# Adafruit_Feather_nRF52840_Rev.net
KiCad netlist of a schematic drawn in EAGLE
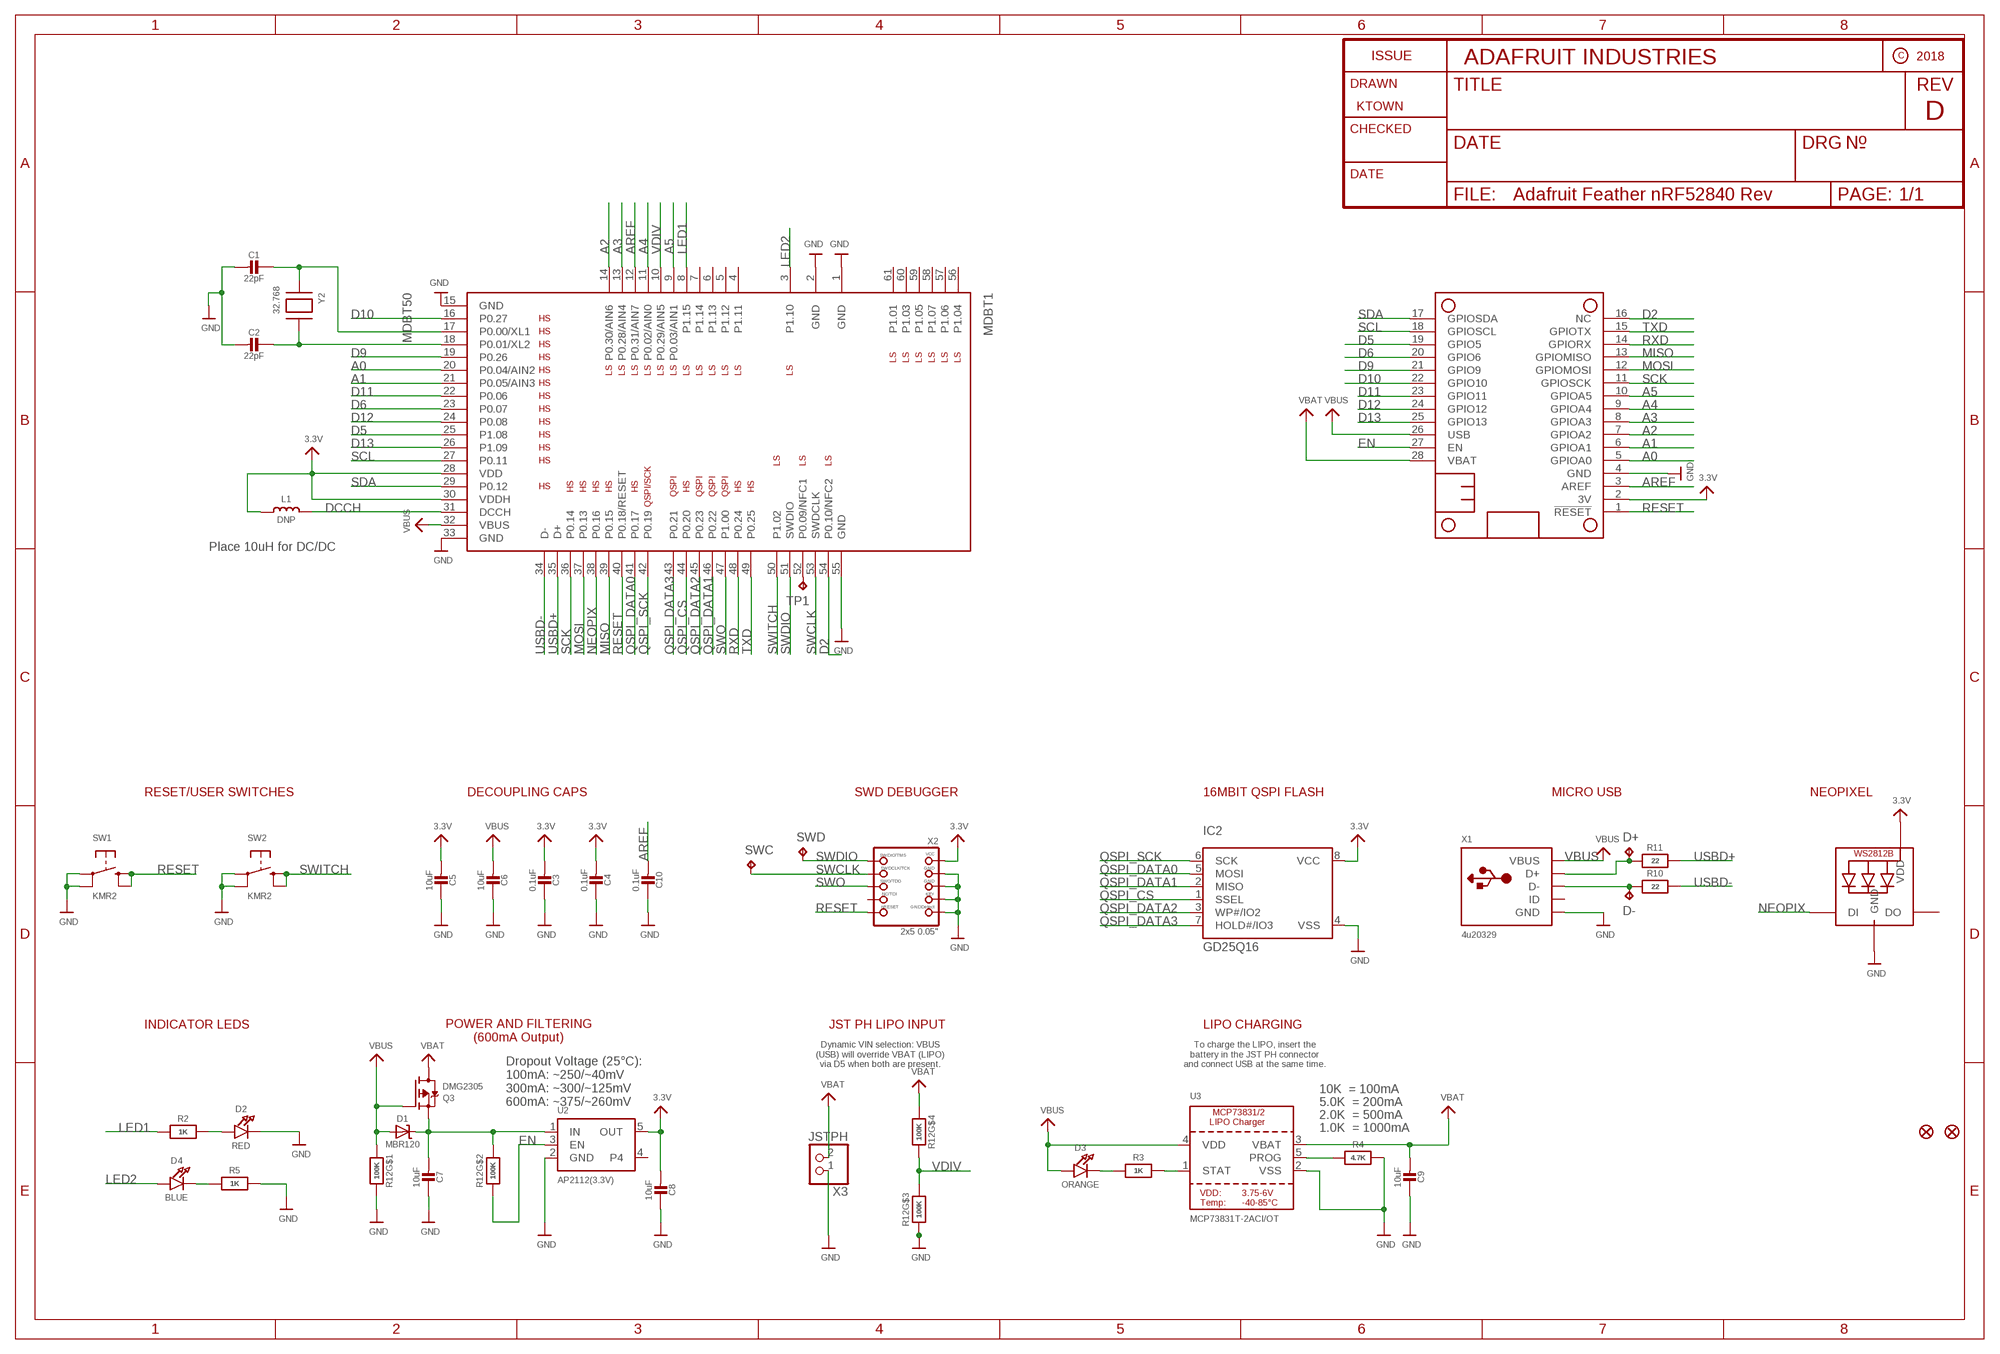
[diagram p0: schematic, sheet 1]

(export (version "E")
  (design (tool "Eeschema 10.0.6"))
  (components
    (comp (ref "C1")
      (value "22pF")
      (footprint "eagle-import:0603-NO")
      (libsource (lib "eagle-import") (part "CAP_CERAMIC0603_NO"))
    )
    (comp (ref "C2")
      (value "22pF")
      (footprint "eagle-import:0603-NO")
      (libsource (lib "eagle-import") (part "CAP_CERAMIC0603_NO"))
    )
    (comp (ref "C3")
      (value "0.1uF")
      (footprint "eagle-import:0603-NO")
      (libsource (lib "eagle-import") (part "CAP_CERAMIC0603_NO"))
    )
    (comp (ref "C4")
      (value "0.1uF")
      (footprint "eagle-import:0603-NO")
      (libsource (lib "eagle-import") (part "CAP_CERAMIC0603_NO"))
    )
    (comp (ref "C5")
      (value "10uF")
      (footprint "eagle-import:0805-NO")
      (libsource (lib "eagle-import") (part "CAP_CERAMIC0805-NOOUTLINE"))
    )
    (comp (ref "C6")
      (value "10uF")
      (footprint "eagle-import:0805-NO")
      (libsource (lib "eagle-import") (part "CAP_CERAMIC0805-NOOUTLINE"))
    )
    (comp (ref "C7")
      (value "10uF")
      (footprint "eagle-import:0805-NO")
      (libsource (lib "eagle-import") (part "CAP_CERAMIC0805-NOOUTLINE"))
    )
    (comp (ref "C8")
      (value "10uF")
      (footprint "eagle-import:0805-NO")
      (libsource (lib "eagle-import") (part "CAP_CERAMIC0805-NOOUTLINE"))
    )
    (comp (ref "C9")
      (value "10uF")
      (footprint "eagle-import:0805-NO")
      (libsource (lib "eagle-import") (part "CAP_CERAMIC0805-NOOUTLINE"))
    )
    (comp (ref "C10")
      (value "0.1uF")
      (footprint "eagle-import:0603-NO")
      (libsource (lib "eagle-import") (part "CAP_CERAMIC0603_NO"))
    )
    (comp (ref "D+")
      (value "TPTP10R")
      (footprint "eagle-import:TP10R")
      (libsource (lib "eagle-import") (part "TPTP10R"))
    )
    (comp (ref "D-")
      (value "TPTP10R")
      (footprint "eagle-import:TP10R")
      (libsource (lib "eagle-import") (part "TPTP10R"))
    )
    (comp (ref "D1")
      (value "MBR120")
      (footprint "eagle-import:SOD-123")
      (libsource (lib "eagle-import") (part "DIODE-SCHOTTKYSOD-123"))
    )
    (comp (ref "D2")
      (value "RED")
      (footprint "eagle-import:CHIPLED_0805_NOOUTLINE")
      (libsource (lib "eagle-import") (part "LED0805_NOOUTLINE"))
    )
    (comp (ref "D3")
      (value "ORANGE")
      (footprint "eagle-import:CHIPLED_0805_NOOUTLINE")
      (libsource (lib "eagle-import") (part "LED0805_NOOUTLINE"))
    )
    (comp (ref "D4")
      (value "BLUE")
      (footprint "eagle-import:CHIPLED_0805_NOOUTLINE")
      (libsource (lib "eagle-import") (part "LED0805_NOOUTLINE"))
    )
    (comp (ref "FID1")
      (value "FIDUCIAL_1MM")
      (footprint "eagle-import:FIDUCIAL_1MM")
      (libsource (lib "eagle-import") (part "FIDUCIAL_1MM"))
    )
    (comp (ref "FID2")
      (value "FIDUCIAL_1MM")
      (footprint "eagle-import:FIDUCIAL_1MM")
      (libsource (lib "eagle-import") (part "FIDUCIAL_1MM"))
    )
    (comp (ref "IC2")
      (value "GD25Q16")
      (footprint "eagle-import:USON8")
      (libsource (lib "eagle-import") (part "SPIFLASH_8PINUX"))
    )
    (comp (ref "L1")
      (value "DNP")
      (footprint "eagle-import:_0805MP")
      (libsource (lib "eagle-import") (part "INDUCTOR_0805MP"))
    )
    (comp (ref "LED1")
      (value "WS2812B3535")
      (footprint "eagle-import:LED3535")
      (libsource (lib "eagle-import") (part "WS2812B3535"))
    )
    (comp (ref "MDBT1")
      (value "MDBT50")
      (footprint "eagle-import:MDBT50")
      (libsource (lib "eagle-import") (part "MDBT50"))
    )
    (comp (ref "MS1")
      (value "FEATHERWING_NODIM")
      (footprint "eagle-import:FEATHERWING_NODIM")
      (libsource (lib "eagle-import") (part "FEATHERWING_NODIM"))
    )
    (comp (ref "Q3")
      (value "DMG2305")
      (footprint "eagle-import:SOT23-R")
      (libsource (lib "eagle-import") (part "MOSFET-P"))
    )
    (comp (ref "R2")
      (value "1K")
      (footprint "eagle-import:0603-NO")
      (libsource (lib "eagle-import") (part "RESISTOR_0603_NOOUT"))
    )
    (comp (ref "R3")
      (value "1K")
      (footprint "eagle-import:0603-NO")
      (libsource (lib "eagle-import") (part "RESISTOR_0603_NOOUT"))
    )
    (comp (ref "R4")
      (value "4.7K")
      (footprint "eagle-import:0603-NO")
      (libsource (lib "eagle-import") (part "RESISTOR_0603_NOOUT"))
    )
    (comp (ref "R5")
      (value "1K")
      (footprint "eagle-import:0603-NO")
      (libsource (lib "eagle-import") (part "RESISTOR_0603_NOOUT"))
    )
    (comp (ref "R10")
      (value "22")
      (footprint "eagle-import:0603-NO")
      (libsource (lib "eagle-import") (part "RESISTOR_0603_NOOUT"))
    )
    (comp (ref "R11")
      (value "22")
      (footprint "eagle-import:0603-NO")
      (libsource (lib "eagle-import") (part "RESISTOR_0603_NOOUT"))
    )
    (comp (ref "R12")
      (value "100K")
      (footprint "eagle-import:RESPACK_4X0603")
      (libsource (lib "eagle-import") (part "RESISTOR_4PACK"))
    )
    (comp (ref "SW1")
      (value "KMR2")
      (footprint "eagle-import:BTN_KMR2_4.6X2.8")
      (libsource (lib "eagle-import") (part "SWITCH_TACT_SMT4.6X2.8"))
    )
    (comp (ref "SW2")
      (value "KMR2")
      (footprint "eagle-import:BTN_KMR2_4.6X2.8")
      (libsource (lib "eagle-import") (part "SWITCH_TACT_SMT4.6X2.8"))
    )
    (comp (ref "SWC")
      (value "TPTP12R")
      (footprint "eagle-import:TP12R")
      (libsource (lib "eagle-import") (part "TPTP12R"))
    )
    (comp (ref "SWD")
      (value "TPTP12R")
      (footprint "eagle-import:TP12R")
      (libsource (lib "eagle-import") (part "TPTP12R"))
    )
    (comp (ref "TP1")
      (value "TPTP10R")
      (footprint "eagle-import:TP10R")
      (libsource (lib "eagle-import") (part "TPTP10R"))
    )
    (comp (ref "U2")
      (value "AP2112(3.3V)")
      (footprint "eagle-import:SOT23-5")
      (libsource (lib "eagle-import") (part "VREG_SOT23-5"))
    )
    (comp (ref "U3")
      (value "MCP73831T-2ACI/OT")
      (footprint "eagle-import:SOT23-5")
      (libsource (lib "eagle-import") (part "MCP73831/2"))
    )
    (comp (ref "X1")
      (value "4u20329")
      (footprint "eagle-import:4UCONN_20329_V2")
      (libsource (lib "eagle-import") (part "USB_MICRO_20329_V2"))
    )
    (comp (ref "X2")
      (value "2x5 0.05\"")
      (footprint "eagle-import:2X05_1.27MM_BOX_POSTS")
      (libsource (lib "eagle-import") (part "JTAG-CORTEXBOXPOSTS"))
    )
    (comp (ref "X3")
      (value "JSTPH")
      (footprint "eagle-import:JSTPH2")
      (libsource (lib "eagle-import") (part "CON_JST_PH_2PIN"))
    )
    (comp (ref "Y2")
      (value "32.768")
      (footprint "eagle-import:XTAL3215")
      (libsource (lib "eagle-import") (part "XTAL-3.2X1.5"))
    )
  )
  (nets
    (net (code "1") (name "/A0") (class "Default")
      (node (ref "MDBT1") (pin "20") (pinfunction "P0.04/AIN2_20") (pintype "bidirectional"))
      (node (ref "MS1") (pin "5") (pinfunction "GPIOA0_5") (pintype "bidirectional"))
    )
    (net (code "2") (name "/A1") (class "Default")
      (node (ref "MDBT1") (pin "21") (pinfunction "P0.05/AIN3_21") (pintype "bidirectional"))
      (node (ref "MS1") (pin "6") (pinfunction "GPIOA1_6") (pintype "bidirectional"))
    )
    (net (code "3") (name "/A2") (class "Default")
      (node (ref "MDBT1") (pin "14") (pinfunction "P0.30/AIN6_14") (pintype "bidirectional"))
      (node (ref "MS1") (pin "7") (pinfunction "GPIOA2_7") (pintype "bidirectional"))
    )
    (net (code "4") (name "/A3") (class "Default")
      (node (ref "MDBT1") (pin "13") (pinfunction "P0.28/AIN4_13") (pintype "bidirectional"))
      (node (ref "MS1") (pin "8") (pinfunction "GPIOA3_8") (pintype "bidirectional"))
    )
    (net (code "5") (name "/A4") (class "Default")
      (node (ref "MDBT1") (pin "11") (pinfunction "P0.02/AIN0_11") (pintype "bidirectional"))
      (node (ref "MS1") (pin "9") (pinfunction "GPIOA4_9") (pintype "bidirectional"))
    )
    (net (code "6") (name "/A5") (class "Default")
      (node (ref "MDBT1") (pin "9") (pinfunction "P0.03/AIN1_9") (pintype "bidirectional"))
      (node (ref "MS1") (pin "10") (pinfunction "GPIOA5_10") (pintype "bidirectional"))
    )
    (net (code "7") (name "/AREF") (class "Default")
      (node (ref "C10") (pin "2") (pinfunction "2_2") (pintype "passive"))
      (node (ref "MDBT1") (pin "12") (pinfunction "P0.31/AIN7_12") (pintype "bidirectional"))
      (node (ref "MS1") (pin "3") (pinfunction "AREF_3") (pintype "passive"))
    )
    (net (code "8") (name "/D2") (class "Default")
      (node (ref "MDBT1") (pin "54") (pinfunction "P0.10/NFC2_54") (pintype "bidirectional"))
      (node (ref "MS1") (pin "16") (pinfunction "NC_16") (pintype "passive"))
    )
    (net (code "9") (name "/D5") (class "Default")
      (node (ref "MDBT1") (pin "25") (pinfunction "P1.08_25") (pintype "bidirectional"))
      (node (ref "MS1") (pin "19") (pinfunction "GPIO5_19") (pintype "bidirectional"))
    )
    (net (code "10") (name "/D6") (class "Default")
      (node (ref "MDBT1") (pin "23") (pinfunction "P0.07_23") (pintype "bidirectional"))
      (node (ref "MS1") (pin "20") (pinfunction "GPIO6_20") (pintype "bidirectional"))
    )
    (net (code "11") (name "/D9") (class "Default")
      (node (ref "MDBT1") (pin "19") (pinfunction "P0.26_19") (pintype "bidirectional"))
      (node (ref "MS1") (pin "21") (pinfunction "GPIO9_21") (pintype "bidirectional"))
    )
    (net (code "12") (name "/D10") (class "Default")
      (node (ref "MDBT1") (pin "16") (pinfunction "P0.27_16") (pintype "bidirectional"))
      (node (ref "MS1") (pin "22") (pinfunction "GPIO10_22") (pintype "bidirectional"))
    )
    (net (code "13") (name "/D11") (class "Default")
      (node (ref "MDBT1") (pin "22") (pinfunction "P0.06_22") (pintype "bidirectional"))
      (node (ref "MS1") (pin "23") (pinfunction "GPIO11_23") (pintype "bidirectional"))
    )
    (net (code "14") (name "/D12") (class "Default")
      (node (ref "MDBT1") (pin "24") (pinfunction "P0.08_24") (pintype "bidirectional"))
      (node (ref "MS1") (pin "24") (pinfunction "GPIO12_24") (pintype "bidirectional"))
    )
    (net (code "15") (name "/D13") (class "Default")
      (node (ref "MDBT1") (pin "26") (pinfunction "P1.09_26") (pintype "bidirectional"))
      (node (ref "MS1") (pin "25") (pinfunction "GPIO13_25") (pintype "bidirectional"))
    )
    (net (code "16") (name "/DCCH") (class "Default")
      (node (ref "L1") (pin "2") (pinfunction "2_2") (pintype "passive"))
      (node (ref "MDBT1") (pin "31") (pinfunction "DCCH_31") (pintype "bidirectional"))
    )
    (net (code "17") (name "/EN") (class "Default")
      (node (ref "MS1") (pin "27") (pinfunction "EN_27") (pintype "passive"))
      (node (ref "R12") (pin "2") (pinfunction "1_2") (pintype "passive"))
      (node (ref "U2") (pin "3") (pinfunction "EN_3") (pintype "input"))
    )
    (net (code "18") (name "/LED1") (class "Default")
      (node (ref "MDBT1") (pin "8") (pinfunction "P1.15_8") (pintype "bidirectional"))
      (node (ref "R2") (pin "1") (pinfunction "1_1") (pintype "passive"))
    )
    (net (code "19") (name "/LED2") (class "Default")
      (node (ref "D4") (pin "A") (pinfunction "A_A") (pintype "passive"))
      (node (ref "MDBT1") (pin "3") (pinfunction "P1.10_3") (pintype "bidirectional"))
    )
    (net (code "20") (name "/MISO") (class "Default")
      (node (ref "MDBT1") (pin "39") (pinfunction "P0.15_39") (pintype "bidirectional"))
      (node (ref "MS1") (pin "13") (pinfunction "GPIOMISO_13") (pintype "bidirectional"))
    )
    (net (code "21") (name "/MOSI") (class "Default")
      (node (ref "MDBT1") (pin "37") (pinfunction "P0.13_37") (pintype "bidirectional"))
      (node (ref "MS1") (pin "12") (pinfunction "GPIOMOSI_12") (pintype "bidirectional"))
    )
    (net (code "22") (name "/NEOPIX") (class "Default")
      (node (ref "LED1") (pin "1") (pinfunction "DI_1") (pintype "input"))
      (node (ref "MDBT1") (pin "38") (pinfunction "P0.16_38") (pintype "bidirectional"))
    )
    (net (code "23") (name "/QSPI_CS") (class "Default")
      (node (ref "IC2") (pin "1") (pinfunction "SSEL_1") (pintype "bidirectional"))
      (node (ref "MDBT1") (pin "44") (pinfunction "P0.20_44") (pintype "bidirectional"))
    )
    (net (code "24") (name "/QSPI_DATA0") (class "Default")
      (node (ref "IC2") (pin "5") (pinfunction "MOSI_5") (pintype "bidirectional"))
      (node (ref "MDBT1") (pin "41") (pinfunction "P0.17_41") (pintype "bidirectional"))
    )
    (net (code "25") (name "/QSPI_DATA1") (class "Default")
      (node (ref "IC2") (pin "2") (pinfunction "MISO_2") (pintype "bidirectional"))
      (node (ref "MDBT1") (pin "46") (pinfunction "P0.22_46") (pintype "bidirectional"))
    )
    (net (code "26") (name "/QSPI_DATA2") (class "Default")
      (node (ref "IC2") (pin "3") (pinfunction "WP#/IO2_3") (pintype "bidirectional"))
      (node (ref "MDBT1") (pin "45") (pinfunction "P0.23_45") (pintype "bidirectional"))
    )
    (net (code "27") (name "/QSPI_DATA3") (class "Default")
      (node (ref "IC2") (pin "7") (pinfunction "HOLD#/IO3_7") (pintype "bidirectional"))
      (node (ref "MDBT1") (pin "43") (pinfunction "P0.21_43") (pintype "bidirectional"))
    )
    (net (code "28") (name "/QSPI_SCK") (class "Default")
      (node (ref "IC2") (pin "6") (pinfunction "SCK_6") (pintype "bidirectional"))
      (node (ref "MDBT1") (pin "42") (pinfunction "P0.19_42") (pintype "bidirectional"))
    )
    (net (code "29") (name "/RESET") (class "Default")
      (node (ref "MDBT1") (pin "40") (pinfunction "P0.18/RESET_40") (pintype "bidirectional"))
      (node (ref "MS1") (pin "1") (pinfunction "~{RESET}_1") (pintype "input"))
      (node (ref "SW1") (pin "B") (pinfunction "S_B") (pintype "passive"))
      (node (ref "SW1") (pin "B'") (pinfunction "S1_B'") (pintype "passive"))
      (node (ref "X2") (pin "10") (pinfunction "NRESET_10") (pintype "bidirectional"))
    )
    (net (code "30") (name "/RXD") (class "Default")
      (node (ref "MDBT1") (pin "48") (pinfunction "P0.24_48") (pintype "bidirectional"))
      (node (ref "MS1") (pin "14") (pinfunction "GPIORX_14") (pintype "bidirectional"))
    )
    (net (code "31") (name "/SCK") (class "Default")
      (node (ref "MDBT1") (pin "36") (pinfunction "P0.14_36") (pintype "bidirectional"))
      (node (ref "MS1") (pin "11") (pinfunction "GPIOSCK_11") (pintype "bidirectional"))
    )
    (net (code "32") (name "/SCL") (class "Default")
      (node (ref "MDBT1") (pin "27") (pinfunction "P0.11_27") (pintype "bidirectional"))
      (node (ref "MS1") (pin "18") (pinfunction "GPIOSCL_18") (pintype "bidirectional"))
    )
    (net (code "33") (name "/SDA") (class "Default")
      (node (ref "MDBT1") (pin "29") (pinfunction "P0.12_29") (pintype "bidirectional"))
      (node (ref "MS1") (pin "17") (pinfunction "GPIOSDA_17") (pintype "bidirectional"))
    )
    (net (code "34") (name "/SWCLK") (class "Default")
      (node (ref "MDBT1") (pin "53") (pinfunction "SWDCLK_53") (pintype "bidirectional"))
      (node (ref "SWC") (pin "TP") (pinfunction "TP_TP") (pintype "input"))
      (node (ref "X2") (pin "4") (pinfunction "SWDCLK_4") (pintype "bidirectional"))
    )
    (net (code "35") (name "/SWDIO") (class "Default")
      (node (ref "MDBT1") (pin "51") (pinfunction "SWDIO_51") (pintype "bidirectional"))
      (node (ref "SWD") (pin "TP") (pinfunction "TP_TP") (pintype "input"))
      (node (ref "X2") (pin "2") (pinfunction "SWDIO_2") (pintype "bidirectional"))
    )
    (net (code "36") (name "/SWITCH") (class "Default")
      (node (ref "MDBT1") (pin "50") (pinfunction "P1.02_50") (pintype "bidirectional"))
      (node (ref "SW2") (pin "B") (pinfunction "S_B") (pintype "passive"))
      (node (ref "SW2") (pin "B'") (pinfunction "S1_B'") (pintype "passive"))
    )
    (net (code "37") (name "/SWO") (class "Default")
      (node (ref "MDBT1") (pin "47") (pinfunction "P1.00_47") (pintype "bidirectional"))
      (node (ref "X2") (pin "6") (pinfunction "SWO_6") (pintype "bidirectional"))
    )
    (net (code "38") (name "/TXD") (class "Default")
      (node (ref "MDBT1") (pin "49") (pinfunction "P0.25_49") (pintype "bidirectional"))
      (node (ref "MS1") (pin "15") (pinfunction "GPIOTX_15") (pintype "bidirectional"))
    )
    (net (code "39") (name "/USBD+") (class "Default")
      (node (ref "MDBT1") (pin "35") (pinfunction "D+_35") (pintype "bidirectional"))
      (node (ref "R11") (pin "2") (pinfunction "2_2") (pintype "passive"))
    )
    (net (code "40") (name "/USBD-") (class "Default")
      (node (ref "MDBT1") (pin "34") (pinfunction "D-_34") (pintype "bidirectional"))
      (node (ref "R10") (pin "2") (pinfunction "2_2") (pintype "passive"))
    )
    (net (code "41") (name "/VDIV") (class "Default")
      (node (ref "MDBT1") (pin "10") (pinfunction "P0.29/AIN5_10") (pintype "bidirectional"))
      (node (ref "R12") (pin "5") (pinfunction "2_5") (pintype "passive"))
      (node (ref "R12") (pin "6") (pinfunction "2_6") (pintype "passive"))
    )
    (net (code "42") (name "3.3V") (class "Default")
      (node (ref "C3") (pin "2") (pinfunction "2_2") (pintype "passive"))
      (node (ref "C4") (pin "2") (pinfunction "2_2") (pintype "passive"))
      (node (ref "C5") (pin "2") (pinfunction "2_2") (pintype "passive"))
      (node (ref "C8") (pin "2") (pinfunction "2_2") (pintype "passive"))
      (node (ref "IC2") (pin "8") (pinfunction "VCC_8") (pintype "bidirectional"))
      (node (ref "L1") (pin "1") (pinfunction "1_1") (pintype "passive"))
      (node (ref "LED1") (pin "2") (pinfunction "VDD_2") (pintype "power_in"))
      (node (ref "MDBT1") (pin "28") (pinfunction "VDD_28") (pintype "bidirectional"))
      (node (ref "MDBT1") (pin "30") (pinfunction "VDDH_30") (pintype "bidirectional"))
      (node (ref "MS1") (pin "2") (pinfunction "3V_2") (pintype "power_in"))
      (node (ref "U2") (pin "5") (pinfunction "OUT_5") (pintype "power_in"))
      (node (ref "X2") (pin "1") (pinfunction "VCC_1") (pintype "power_in"))
    )
    (net (code "43") (name "GND") (class "Default")
      (node (ref "C1") (pin "2") (pinfunction "2_2") (pintype "passive"))
      (node (ref "C10") (pin "1") (pinfunction "1_1") (pintype "passive"))
      (node (ref "C2") (pin "2") (pinfunction "2_2") (pintype "passive"))
      (node (ref "C3") (pin "1") (pinfunction "1_1") (pintype "passive"))
      (node (ref "C4") (pin "1") (pinfunction "1_1") (pintype "passive"))
      (node (ref "C5") (pin "1") (pinfunction "1_1") (pintype "passive"))
      (node (ref "C6") (pin "1") (pinfunction "1_1") (pintype "passive"))
      (node (ref "C7") (pin "1") (pinfunction "1_1") (pintype "passive"))
      (node (ref "C8") (pin "1") (pinfunction "1_1") (pintype "passive"))
      (node (ref "C9") (pin "1") (pinfunction "1_1") (pintype "passive"))
      (node (ref "D2") (pin "C") (pinfunction "C_C") (pintype "passive"))
      (node (ref "IC2") (pin "4") (pinfunction "VSS_4") (pintype "bidirectional"))
      (node (ref "LED1") (pin "4") (pinfunction "GND_4") (pintype "power_in"))
      (node (ref "MDBT1") (pin "1") (pinfunction "GND_1") (pintype "bidirectional"))
      (node (ref "MDBT1") (pin "15") (pinfunction "GND_15") (pintype "bidirectional"))
      (node (ref "MDBT1") (pin "2") (pinfunction "GND_2") (pintype "bidirectional"))
      (node (ref "MDBT1") (pin "33") (pinfunction "GND_33") (pintype "bidirectional"))
      (node (ref "MDBT1") (pin "55") (pinfunction "GND_55") (pintype "bidirectional"))
      (node (ref "MS1") (pin "4") (pinfunction "GND_4") (pintype "power_in"))
      (node (ref "R12") (pin "3") (pinfunction "1_3") (pintype "passive"))
      (node (ref "R12") (pin "8") (pinfunction "2_8") (pintype "passive"))
      (node (ref "R4") (pin "2") (pinfunction "2_2") (pintype "passive"))
      (node (ref "R5") (pin "2") (pinfunction "2_2") (pintype "passive"))
      (node (ref "SW1") (pin "A") (pinfunction "P_A") (pintype "passive"))
      (node (ref "SW1") (pin "A'") (pinfunction "P1_A'") (pintype "passive"))
      (node (ref "SW2") (pin "A") (pinfunction "P_A") (pintype "passive"))
      (node (ref "SW2") (pin "A'") (pinfunction "P1_A'") (pintype "passive"))
      (node (ref "U2") (pin "2") (pinfunction "GND_2") (pintype "power_in"))
      (node (ref "U3") (pin "2") (pinfunction "VSS_2") (pintype "power_in"))
      (node (ref "X1") (pin "BASE@1") (pinfunction "GND_BASE@1") (pintype "power_in"))
      (node (ref "X1") (pin "BASE@2") (pinfunction "GND_BASE@2") (pintype "power_in"))
      (node (ref "X1") (pin "GND") (pinfunction "GND_GND") (pintype "power_in"))
      (node (ref "X1") (pin "SPRT@1") (pinfunction "GND_SPRT@1") (pintype "power_in"))
      (node (ref "X1") (pin "SPRT@2") (pinfunction "GND_SPRT@2") (pintype "power_in"))
      (node (ref "X1") (pin "SPRT@3") (pinfunction "GND_SPRT@3") (pintype "power_in"))
      (node (ref "X1") (pin "SPRT@4") (pinfunction "GND_SPRT@4") (pintype "power_in"))
      (node (ref "X2") (pin "3") (pinfunction "GND_3") (pintype "power_in"))
      (node (ref "X2") (pin "5") (pinfunction "GND_5") (pintype "power_in"))
      (node (ref "X2") (pin "7") (pinfunction "KEY_7") (pintype "bidirectional"))
      (node (ref "X2") (pin "9") (pinfunction "GNDDETECT_9") (pintype "bidirectional"))
      (node (ref "X3") (pin "1") (pinfunction "1_1") (pintype "passive"))
    )
    (net (code "44") (name "Net-(D+-PadTP)") (class "Default")
      (node (ref "D+") (pin "TP") (pinfunction "TP_TP") (pintype "input"))
      (node (ref "R11") (pin "1") (pinfunction "1_1") (pintype "passive"))
      (node (ref "X1") (pin "D+") (pinfunction "D+_D+") (pintype "bidirectional"))
    )
    (net (code "45") (name "Net-(D--PadTP)") (class "Default")
      (node (ref "D-") (pin "TP") (pinfunction "TP_TP") (pintype "input"))
      (node (ref "R10") (pin "1") (pinfunction "1_1") (pintype "passive"))
      (node (ref "X1") (pin "D-") (pinfunction "D-_D-") (pintype "bidirectional"))
    )
    (net (code "46") (name "Net-(D2-PadA)") (class "Default")
      (node (ref "D2") (pin "A") (pinfunction "A_A") (pintype "passive"))
      (node (ref "R2") (pin "2") (pinfunction "2_2") (pintype "passive"))
    )
    (net (code "47") (name "Net-(D3-PadC)") (class "Default")
      (node (ref "D3") (pin "C") (pinfunction "C_C") (pintype "passive"))
      (node (ref "R3") (pin "1") (pinfunction "1_1") (pintype "passive"))
    )
    (net (code "48") (name "Net-(D4-PadC)") (class "Default")
      (node (ref "D4") (pin "C") (pinfunction "C_C") (pintype "passive"))
      (node (ref "R5") (pin "1") (pinfunction "1_1") (pintype "passive"))
    )
    (net (code "49") (name "Net-(MDBT1-P0.00{slash}XL1)") (class "Default")
      (node (ref "C1") (pin "1") (pinfunction "1_1") (pintype "passive"))
      (node (ref "MDBT1") (pin "17") (pinfunction "P0.00/XL1_17") (pintype "bidirectional"))
      (node (ref "Y2") (pin "P$1") (pinfunction "P$1_P$1") (pintype "bidirectional"))
    )
    (net (code "50") (name "Net-(MDBT1-P0.01{slash}XL2)") (class "Default")
      (node (ref "C2") (pin "1") (pinfunction "1_1") (pintype "passive"))
      (node (ref "MDBT1") (pin "18") (pinfunction "P0.01/XL2_18") (pintype "bidirectional"))
      (node (ref "Y2") (pin "P$2") (pinfunction "P$2_P$2") (pintype "bidirectional"))
    )
    (net (code "51") (name "Net-(MDBT1-P0.09{slash}NFC1)") (class "Default")
      (node (ref "MDBT1") (pin "52") (pinfunction "P0.09/NFC1_52") (pintype "bidirectional"))
      (node (ref "TP1") (pin "TP") (pinfunction "TP_TP") (pintype "input"))
    )
    (net (code "52") (name "Net-(Q3-S)") (class "Default")
      (node (ref "C7") (pin "2") (pinfunction "2_2") (pintype "passive"))
      (node (ref "D1") (pin "C") (pinfunction "C_C") (pintype "passive"))
      (node (ref "Q3") (pin "2") (pinfunction "S_2") (pintype "passive"))
      (node (ref "R12") (pin "7") (pinfunction "2_7") (pintype "passive"))
      (node (ref "U2") (pin "1") (pinfunction "IN_1") (pintype "power_in"))
    )
    (net (code "53") (name "Net-(U3-PROG)") (class "Default")
      (node (ref "R4") (pin "1") (pinfunction "1_1") (pintype "passive"))
      (node (ref "U3") (pin "5") (pinfunction "PROG_5") (pintype "input"))
    )
    (net (code "54") (name "Net-(U3-STAT)") (class "Default")
      (node (ref "R3") (pin "2") (pinfunction "2_2") (pintype "passive"))
      (node (ref "U3") (pin "1") (pinfunction "STAT_1") (pintype "output"))
    )
    (net (code "55") (name "VBAT") (class "Default")
      (node (ref "C9") (pin "2") (pinfunction "2_2") (pintype "passive"))
      (node (ref "MS1") (pin "28") (pinfunction "VBAT_28") (pintype "power_in"))
      (node (ref "Q3") (pin "3") (pinfunction "D_3") (pintype "passive"))
      (node (ref "R12") (pin "4") (pinfunction "1_4") (pintype "passive"))
      (node (ref "U3") (pin "3") (pinfunction "VBAT_3") (pintype "power_in"))
      (node (ref "X3") (pin "2") (pinfunction "2_2") (pintype "passive"))
    )
    (net (code "56") (name "VBUS") (class "Default")
      (node (ref "C6") (pin "2") (pinfunction "2_2") (pintype "passive"))
      (node (ref "D1") (pin "A") (pinfunction "A_A") (pintype "passive"))
      (node (ref "D3") (pin "A") (pinfunction "A_A") (pintype "passive"))
      (node (ref "MDBT1") (pin "32") (pinfunction "VBUS_32") (pintype "bidirectional"))
      (node (ref "MS1") (pin "26") (pinfunction "USB_26") (pintype "power_in"))
      (node (ref "Q3") (pin "1") (pinfunction "G_1") (pintype "passive"))
      (node (ref "R12") (pin "1") (pinfunction "1_1") (pintype "passive"))
      (node (ref "U3") (pin "4") (pinfunction "VDD_4") (pintype "power_in"))
      (node (ref "X1") (pin "VBUS") (pinfunction "VBUS_VBUS") (pintype "power_in"))
    )
    (net (code "57") (name "unconnected-(LED1-DO-Pad3)") (class "Default")
      (node (ref "LED1") (pin "3") (pinfunction "DO_3") (pintype "output"))
    )
    (net (code "58") (name "unconnected-(MDBT1-P1.01-Pad61)") (class "Default")
      (node (ref "MDBT1") (pin "61") (pinfunction "P1.01_61") (pintype "bidirectional"))
    )
    (net (code "59") (name "unconnected-(MDBT1-P1.03-Pad60)") (class "Default")
      (node (ref "MDBT1") (pin "60") (pinfunction "P1.03_60") (pintype "bidirectional"))
    )
    (net (code "60") (name "unconnected-(MDBT1-P1.04-Pad56)") (class "Default")
      (node (ref "MDBT1") (pin "56") (pinfunction "P1.04_56") (pintype "bidirectional"))
    )
    (net (code "61") (name "unconnected-(MDBT1-P1.05-Pad59)") (class "Default")
      (node (ref "MDBT1") (pin "59") (pinfunction "P1.05_59") (pintype "bidirectional"))
    )
    (net (code "62") (name "unconnected-(MDBT1-P1.06-Pad57)") (class "Default")
      (node (ref "MDBT1") (pin "57") (pinfunction "P1.06_57") (pintype "bidirectional"))
    )
    (net (code "63") (name "unconnected-(MDBT1-P1.07-Pad58)") (class "Default")
      (node (ref "MDBT1") (pin "58") (pinfunction "P1.07_58") (pintype "bidirectional"))
    )
    (net (code "64") (name "unconnected-(MDBT1-P1.11-Pad4)") (class "Default")
      (node (ref "MDBT1") (pin "4") (pinfunction "P1.11_4") (pintype "bidirectional"))
    )
    (net (code "65") (name "unconnected-(MDBT1-P1.12-Pad5)") (class "Default")
      (node (ref "MDBT1") (pin "5") (pinfunction "P1.12_5") (pintype "bidirectional"))
    )
    (net (code "66") (name "unconnected-(MDBT1-P1.13-Pad6)") (class "Default")
      (node (ref "MDBT1") (pin "6") (pinfunction "P1.13_6") (pintype "bidirectional"))
    )
    (net (code "67") (name "unconnected-(MDBT1-P1.14-Pad7)") (class "Default")
      (node (ref "MDBT1") (pin "7") (pinfunction "P1.14_7") (pintype "bidirectional"))
    )
    (net (code "68") (name "unconnected-(U2-P4-Pad4)") (class "Default")
      (node (ref "U2") (pin "4") (pinfunction "P4_4") (pintype "bidirectional"))
    )
    (net (code "69") (name "unconnected-(X1-PadID)") (class "Default")
      (node (ref "X1") (pin "ID") (pinfunction "ID_ID") (pintype "bidirectional"))
    )
    (net (code "70") (name "unconnected-(X2-TDI-Pad8)") (class "Default")
      (node (ref "X2") (pin "8") (pinfunction "TDI_8") (pintype "bidirectional"))
    )
  )
)
